# espnative-deadrail-2-1.net
KiCad netlist of a schematic drawn in EAGLE
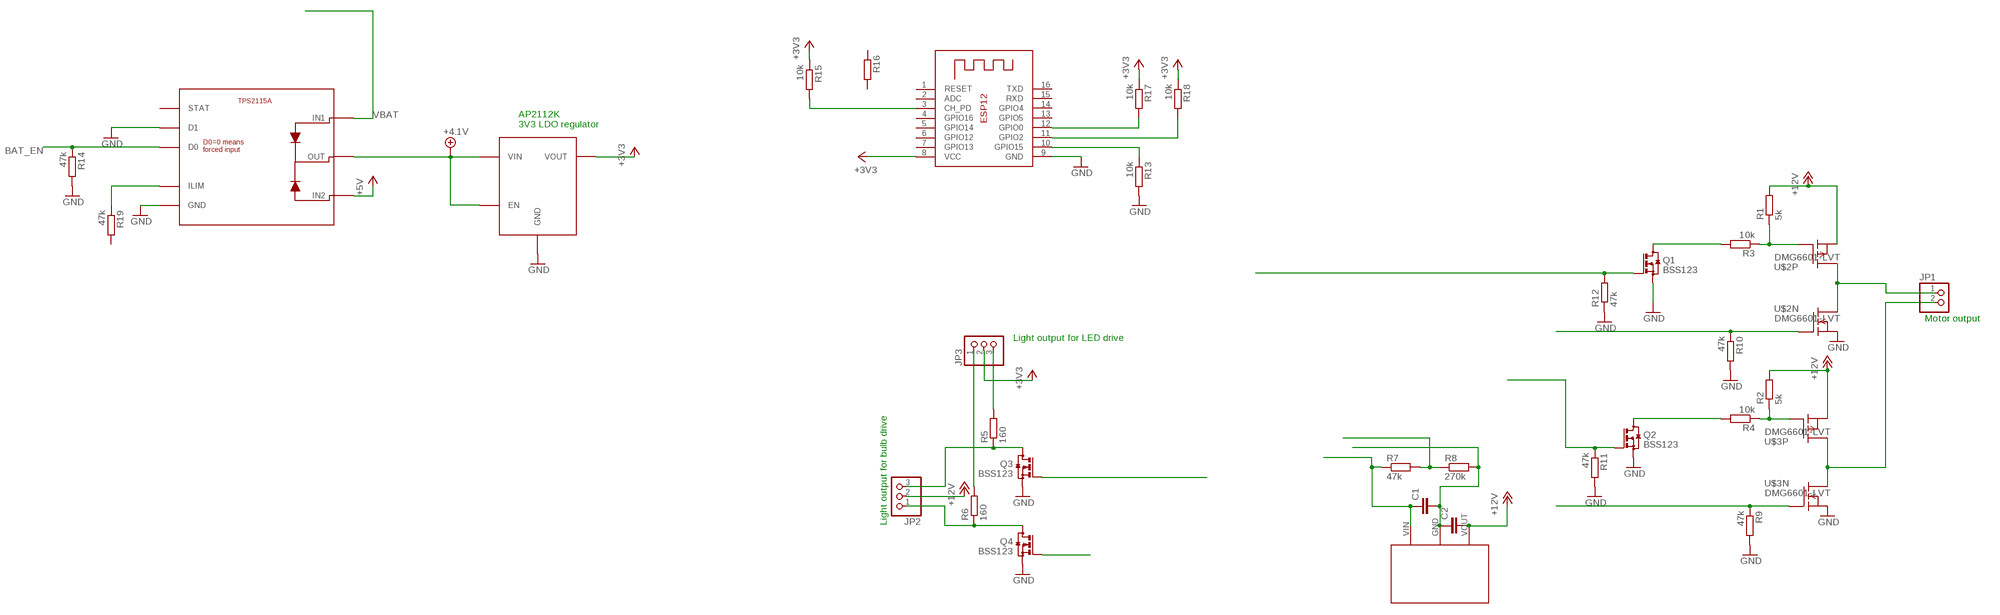
[diagram p0: schematic, sheet 1]

(export (version "E")
  (design (tool "Eeschema 10.0.6"))
  (components
    (comp (ref "C1")
      (value "C-EUC1210")
      (footprint "eagle-import:C1210")
      (libsource (lib "eagle-import") (part "C-EUC1210"))
    )
    (comp (ref "C2")
      (value "C-EUC1210")
      (footprint "eagle-import:C1210")
      (libsource (lib "eagle-import") (part "C-EUC1210"))
    )
    (comp (ref "JP1")
      (value "PINHD-1X2")
      (footprint "eagle-import:1X02")
      (libsource (lib "eagle-import") (part "PINHD-1X2"))
    )
    (comp (ref "JP2")
      (value "PINHD-1X3")
      (footprint "eagle-import:1X03")
      (libsource (lib "eagle-import") (part "PINHD-1X3"))
    )
    (comp (ref "JP3")
      (value "PINHD-1X3")
      (footprint "eagle-import:1X03")
      (libsource (lib "eagle-import") (part "PINHD-1X3"))
    )
    (comp (ref "Q1")
      (value "BSS123")
      (footprint "eagle-import:SOT23")
      (libsource (lib "eagle-import") (part "BSS123"))
    )
    (comp (ref "Q2")
      (value "BSS123")
      (footprint "eagle-import:SOT23")
      (libsource (lib "eagle-import") (part "BSS123"))
    )
    (comp (ref "Q3")
      (value "BSS123")
      (footprint "eagle-import:SOT23")
      (libsource (lib "eagle-import") (part "BSS123"))
    )
    (comp (ref "Q4")
      (value "BSS123")
      (footprint "eagle-import:SOT23")
      (libsource (lib "eagle-import") (part "BSS123"))
    )
    (comp (ref "R1")
      (value "5k")
      (footprint "eagle-import:R0805")
      (libsource (lib "eagle-import") (part "R-EU_R0805"))
    )
    (comp (ref "R2")
      (value "5k")
      (footprint "eagle-import:R0805")
      (libsource (lib "eagle-import") (part "R-EU_R0805"))
    )
    (comp (ref "R3")
      (value "10k")
      (footprint "eagle-import:R0805")
      (libsource (lib "eagle-import") (part "R-EU_R0805"))
    )
    (comp (ref "R4")
      (value "10k")
      (footprint "eagle-import:R0805")
      (libsource (lib "eagle-import") (part "R-EU_R0805"))
    )
    (comp (ref "R5")
      (value "160")
      (footprint "eagle-import:R0805")
      (libsource (lib "eagle-import") (part "R-EU_R0805"))
    )
    (comp (ref "R6")
      (value "160")
      (footprint "eagle-import:R0805")
      (libsource (lib "eagle-import") (part "R-EU_R0805"))
    )
    (comp (ref "R7")
      (value "47k")
      (footprint "eagle-import:R0805")
      (libsource (lib "eagle-import") (part "R-EU_R0805"))
    )
    (comp (ref "R8")
      (value "270k")
      (footprint "eagle-import:R0805")
      (libsource (lib "eagle-import") (part "R-EU_R0805"))
    )
    (comp (ref "R9")
      (value "47k")
      (footprint "eagle-import:R0805")
      (libsource (lib "eagle-import") (part "R-EU_R0805"))
    )
    (comp (ref "R10")
      (value "47k")
      (footprint "eagle-import:R0805")
      (libsource (lib "eagle-import") (part "R-EU_R0805"))
    )
    (comp (ref "R11")
      (value "47k")
      (footprint "eagle-import:R0805")
      (libsource (lib "eagle-import") (part "R-EU_R0805"))
    )
    (comp (ref "R12")
      (value "47k")
      (footprint "eagle-import:R0805")
      (libsource (lib "eagle-import") (part "R-EU_R0805"))
    )
    (comp (ref "R13")
      (value "10k")
      (footprint "eagle-import:R0603")
      (libsource (lib "eagle-import") (part "R-EU_R0603"))
    )
    (comp (ref "R14")
      (value "47k")
      (footprint "eagle-import:R0603")
      (libsource (lib "eagle-import") (part "R-EU_R0603"))
    )
    (comp (ref "R15")
      (value "10k")
      (footprint "eagle-import:R0603")
      (libsource (lib "eagle-import") (part "R-EU_R0603"))
    )
    (comp (ref "R16")
      (value "R-EU_R0603")
      (footprint "eagle-import:R0603")
      (libsource (lib "eagle-import") (part "R-EU_R0603"))
    )
    (comp (ref "R17")
      (value "10k")
      (footprint "eagle-import:R0603")
      (libsource (lib "eagle-import") (part "R-EU_R0603"))
    )
    (comp (ref "R18")
      (value "10k")
      (footprint "eagle-import:R0603")
      (libsource (lib "eagle-import") (part "R-EU_R0603"))
    )
    (comp (ref "R19")
      (value "47k")
      (footprint "eagle-import:R0603")
      (libsource (lib "eagle-import") (part "R-EU_R0603"))
    )
    (comp (ref "U$1")
      (value "AP2112K-3V3")
      (footprint "eagle-import:SOT23-5L")
      (libsource (lib "eagle-import") (part "AP2112K"))
    )
    (comp (ref "U$2")
      (value "DMG6601-LVT")
      (footprint "eagle-import:TSOT-26")
      (libsource (lib "eagle-import") (part "DMG6601-LVT"))
    )
    (comp (ref "U$3")
      (value "DMG6601-LVT")
      (footprint "eagle-import:TSOT-26")
      (libsource (lib "eagle-import") (part "DMG6601-LVT"))
    )
    (comp (ref "U$4")
      (value "TPS2115A")
      (footprint "eagle-import:TSSOP-8")
      (libsource (lib "eagle-import") (part "TPS2115A"))
    )
    (comp (ref "U$5")
      (value "POLOLU-VREG12")
      (footprint "eagle-import:POLOLU-REGULATOR")
      (libsource (lib "eagle-import") (part "POLOLU-VREG12"))
    )
    (comp (ref "X1")
      (value "ESP-12")
      (footprint "eagle-import:ESP-12")
      (libsource (lib "eagle-import") (part "ESP-12"))
    )
  )
  (nets
    (net (code "1") (name "+3V3") (class "Default")
      (node (ref "JP3") (pin "2") (pinfunction "2_2") (pintype "passive"))
      (node (ref "R15") (pin "1") (pinfunction "1_1") (pintype "passive"))
      (node (ref "R17") (pin "1") (pinfunction "1_1") (pintype "passive"))
      (node (ref "R18") (pin "1") (pinfunction "1_1") (pintype "passive"))
      (node (ref "U$1") (pin "5") (pinfunction "VOUT_5") (pintype "bidirectional"))
      (node (ref "X1") (pin "8") (pinfunction "VCC_8") (pintype "power_in"))
    )
    (net (code "2") (name "+4.1V") (class "Default")
      (node (ref "U$1") (pin "1") (pinfunction "VIN_1") (pintype "bidirectional"))
      (node (ref "U$1") (pin "3") (pinfunction "EN_3") (pintype "bidirectional"))
      (node (ref "U$4") (pin "7") (pinfunction "OUT_7") (pintype "bidirectional"))
    )
    (net (code "3") (name "+5V") (class "Default")
      (node (ref "U$4") (pin "6") (pinfunction "IN2_6") (pintype "bidirectional"))
    )
    (net (code "4") (name "+12V") (class "Default")
      (node (ref "C2") (pin "2") (pinfunction "2_2") (pintype "passive"))
      (node (ref "JP2") (pin "2") (pinfunction "2_2") (pintype "passive"))
      (node (ref "R1") (pin "2") (pinfunction "2_2") (pintype "passive"))
      (node (ref "R2") (pin "2") (pinfunction "2_2") (pintype "passive"))
      (node (ref "U$2") (pin "2") (pinfunction "S_2") (pintype "passive"))
      (node (ref "U$3") (pin "2") (pinfunction "S_2") (pintype "passive"))
      (node (ref "U$5") (pin "VOUT") (pinfunction "VOUT_VOUT") (pintype "bidirectional"))
    )
    (net (code "5") (name "/BAT_EN") (class "Default")
      (node (ref "R14") (pin "1") (pinfunction "1_1") (pintype "passive"))
      (node (ref "U$4") (pin "2") (pinfunction "D0_2") (pintype "bidirectional"))
    )
    (net (code "6") (name "/VBAT") (class "Default")
      (node (ref "C1") (pin "1") (pinfunction "1_1") (pintype "passive"))
      (node (ref "R7") (pin "1") (pinfunction "1_1") (pintype "passive"))
      (node (ref "U$4") (pin "8") (pinfunction "IN1_8") (pintype "bidirectional"))
      (node (ref "U$5") (pin "VIN") (pinfunction "VIN_VIN") (pintype "bidirectional"))
    )
    (net (code "7") (name "GND") (class "Default")
      (node (ref "C1") (pin "2") (pinfunction "2_2") (pintype "passive"))
      (node (ref "C2") (pin "1") (pinfunction "1_1") (pintype "passive"))
      (node (ref "Q1") (pin "2") (pinfunction "S_2") (pintype "passive"))
      (node (ref "Q2") (pin "2") (pinfunction "S_2") (pintype "passive"))
      (node (ref "Q3") (pin "2") (pinfunction "S_2") (pintype "passive"))
      (node (ref "Q4") (pin "2") (pinfunction "S_2") (pintype "passive"))
      (node (ref "R10") (pin "2") (pinfunction "2_2") (pintype "passive"))
      (node (ref "R11") (pin "2") (pinfunction "2_2") (pintype "passive"))
      (node (ref "R12") (pin "1") (pinfunction "1_1") (pintype "passive"))
      (node (ref "R13") (pin "2") (pinfunction "2_2") (pintype "passive"))
      (node (ref "R14") (pin "2") (pinfunction "2_2") (pintype "passive"))
      (node (ref "R8") (pin "2") (pinfunction "2_2") (pintype "passive"))
      (node (ref "R9") (pin "2") (pinfunction "2_2") (pintype "passive"))
      (node (ref "U$1") (pin "2") (pinfunction "GND_2") (pintype "bidirectional"))
      (node (ref "U$2") (pin "5") (pinfunction "S_5") (pintype "passive"))
      (node (ref "U$3") (pin "5") (pinfunction "S_5") (pintype "passive"))
      (node (ref "U$4") (pin "3") (pinfunction "D1_3") (pintype "bidirectional"))
      (node (ref "U$4") (pin "5") (pinfunction "GND_5") (pintype "bidirectional"))
      (node (ref "U$5") (pin "GND") (pinfunction "GND_GND") (pintype "bidirectional"))
      (node (ref "X1") (pin "9") (pinfunction "GND_9") (pintype "power_in"))
    )
    (net (code "8") (name "Net-(JP3-Pad1)") (class "Default")
      (node (ref "JP3") (pin "1") (pinfunction "1_1") (pintype "passive"))
      (node (ref "R6") (pin "2") (pinfunction "2_2") (pintype "passive"))
    )
    (net (code "9") (name "Net-(JP3-Pad3)") (class "Default")
      (node (ref "JP3") (pin "3") (pinfunction "3_3") (pintype "passive"))
      (node (ref "R5") (pin "2") (pinfunction "2_2") (pintype "passive"))
    )
    (net (code "10") (name "Net-(Q1-D)") (class "Default")
      (node (ref "Q1") (pin "3") (pinfunction "D_3") (pintype "passive"))
      (node (ref "R3") (pin "2") (pinfunction "2_2") (pintype "passive"))
    )
    (net (code "11") (name "Net-(Q1-G)") (class "Default")
      (node (ref "Q1") (pin "1") (pinfunction "G_1") (pintype "passive"))
      (node (ref "R12") (pin "2") (pinfunction "2_2") (pintype "passive"))
    )
    (net (code "12") (name "Net-(Q2-D)") (class "Default")
      (node (ref "Q2") (pin "3") (pinfunction "D_3") (pintype "passive"))
      (node (ref "R4") (pin "2") (pinfunction "2_2") (pintype "passive"))
    )
    (net (code "13") (name "Net-(Q2-G)") (class "Default")
      (node (ref "Q2") (pin "1") (pinfunction "G_1") (pintype "passive"))
      (node (ref "R11") (pin "1") (pinfunction "1_1") (pintype "passive"))
    )
    (net (code "14") (name "Net-(Q3-D)") (class "Default")
      (node (ref "JP2") (pin "3") (pinfunction "3_3") (pintype "passive"))
      (node (ref "Q3") (pin "3") (pinfunction "D_3") (pintype "passive"))
      (node (ref "R5") (pin "1") (pinfunction "1_1") (pintype "passive"))
    )
    (net (code "15") (name "Net-(Q4-D)") (class "Default")
      (node (ref "JP2") (pin "1") (pinfunction "1_1") (pintype "passive"))
      (node (ref "Q4") (pin "3") (pinfunction "D_3") (pintype "passive"))
      (node (ref "R6") (pin "1") (pinfunction "1_1") (pintype "passive"))
    )
    (net (code "16") (name "Net-(R7-Pad2)") (class "Default")
      (node (ref "R7") (pin "2") (pinfunction "2_2") (pintype "passive"))
      (node (ref "R8") (pin "1") (pinfunction "1_1") (pintype "passive"))
    )
    (net (code "17") (name "Net-(U$2A-D)") (class "Default")
      (node (ref "JP1") (pin "1") (pinfunction "1_1") (pintype "passive"))
      (node (ref "U$2") (pin "4") (pinfunction "D_4") (pintype "passive"))
      (node (ref "U$2") (pin "6") (pinfunction "D_6") (pintype "passive"))
    )
    (net (code "18") (name "Net-(U$2A-G)") (class "Default")
      (node (ref "R10") (pin "1") (pinfunction "1_1") (pintype "passive"))
      (node (ref "U$2") (pin "1") (pinfunction "G_1") (pintype "passive"))
    )
    (net (code "19") (name "Net-(U$2B-G)") (class "Default")
      (node (ref "R1") (pin "1") (pinfunction "1_1") (pintype "passive"))
      (node (ref "R3") (pin "1") (pinfunction "1_1") (pintype "passive"))
      (node (ref "U$2") (pin "3") (pinfunction "G_3") (pintype "passive"))
    )
    (net (code "20") (name "Net-(U$3A-D)") (class "Default")
      (node (ref "JP1") (pin "2") (pinfunction "2_2") (pintype "passive"))
      (node (ref "U$3") (pin "4") (pinfunction "D_4") (pintype "passive"))
      (node (ref "U$3") (pin "6") (pinfunction "D_6") (pintype "passive"))
    )
    (net (code "21") (name "Net-(U$3A-G)") (class "Default")
      (node (ref "R9") (pin "1") (pinfunction "1_1") (pintype "passive"))
      (node (ref "U$3") (pin "1") (pinfunction "G_1") (pintype "passive"))
    )
    (net (code "22") (name "Net-(U$3B-G)") (class "Default")
      (node (ref "R2") (pin "1") (pinfunction "1_1") (pintype "passive"))
      (node (ref "R4") (pin "1") (pinfunction "1_1") (pintype "passive"))
      (node (ref "U$3") (pin "3") (pinfunction "G_3") (pintype "passive"))
    )
    (net (code "23") (name "Net-(U$4-ILIM)") (class "Default")
      (node (ref "R19") (pin "1") (pinfunction "1_1") (pintype "passive"))
      (node (ref "U$4") (pin "4") (pinfunction "ILIM_4") (pintype "bidirectional"))
    )
    (net (code "24") (name "Net-(X1-CH_PD)") (class "Default")
      (node (ref "R15") (pin "2") (pinfunction "2_2") (pintype "passive"))
      (node (ref "X1") (pin "3") (pinfunction "CH_PD_3") (pintype "input"))
    )
    (net (code "25") (name "Net-(X1-GPIO0)") (class "Default")
      (node (ref "R17") (pin "2") (pinfunction "2_2") (pintype "passive"))
      (node (ref "X1") (pin "12") (pinfunction "GPIO0_12") (pintype "bidirectional"))
    )
    (net (code "26") (name "Net-(X1-GPIO2)") (class "Default")
      (node (ref "R18") (pin "2") (pinfunction "2_2") (pintype "passive"))
      (node (ref "X1") (pin "11") (pinfunction "GPIO2_11") (pintype "bidirectional"))
    )
    (net (code "27") (name "Net-(X1-GPIO15)") (class "Default")
      (node (ref "R13") (pin "1") (pinfunction "1_1") (pintype "passive"))
      (node (ref "X1") (pin "10") (pinfunction "GPIO15_10") (pintype "bidirectional"))
    )
    (net (code "28") (name "unconnected-(Q3-G-Pad1)") (class "Default")
      (node (ref "Q3") (pin "1") (pinfunction "G_1") (pintype "passive"))
    )
    (net (code "29") (name "unconnected-(Q4-G-Pad1)") (class "Default")
      (node (ref "Q4") (pin "1") (pinfunction "G_1") (pintype "passive"))
    )
    (net (code "30") (name "unconnected-(R16-Pad1)") (class "Default")
      (node (ref "R16") (pin "1") (pinfunction "1_1") (pintype "passive"))
    )
    (net (code "31") (name "unconnected-(R16-Pad2)") (class "Default")
      (node (ref "R16") (pin "2") (pinfunction "2_2") (pintype "passive"))
    )
    (net (code "32") (name "unconnected-(R19-Pad2)") (class "Default")
      (node (ref "R19") (pin "2") (pinfunction "2_2") (pintype "passive"))
    )
    (net (code "33") (name "unconnected-(U$4-STAT-Pad1)") (class "Default")
      (node (ref "U$4") (pin "1") (pinfunction "STAT_1") (pintype "bidirectional"))
    )
    (net (code "34") (name "unconnected-(X1-ADC-Pad2)") (class "Default")
      (node (ref "X1") (pin "2") (pinfunction "ADC_2") (pintype "passive"))
    )
    (net (code "35") (name "unconnected-(X1-GPIO4-Pad14)") (class "Default")
      (node (ref "X1") (pin "14") (pinfunction "GPIO4_14") (pintype "bidirectional"))
    )
    (net (code "36") (name "unconnected-(X1-GPIO5-Pad13)") (class "Default")
      (node (ref "X1") (pin "13") (pinfunction "GPIO5_13") (pintype "bidirectional"))
    )
    (net (code "37") (name "unconnected-(X1-GPIO12-Pad6)") (class "Default")
      (node (ref "X1") (pin "6") (pinfunction "GPIO12_6") (pintype "bidirectional"))
    )
    (net (code "38") (name "unconnected-(X1-GPIO13-Pad7)") (class "Default")
      (node (ref "X1") (pin "7") (pinfunction "GPIO13_7") (pintype "bidirectional"))
    )
    (net (code "39") (name "unconnected-(X1-GPIO14-Pad5)") (class "Default")
      (node (ref "X1") (pin "5") (pinfunction "GPIO14_5") (pintype "bidirectional"))
    )
    (net (code "40") (name "unconnected-(X1-GPIO16-Pad4)") (class "Default")
      (node (ref "X1") (pin "4") (pinfunction "GPIO16_4") (pintype "bidirectional"))
    )
    (net (code "41") (name "unconnected-(X1-RESET-Pad1)") (class "Default")
      (node (ref "X1") (pin "1") (pinfunction "RESET_1") (pintype "input"))
    )
    (net (code "42") (name "unconnected-(X1-RXD-Pad15)") (class "Default")
      (node (ref "X1") (pin "15") (pinfunction "RXD_15") (pintype "input"))
    )
    (net (code "43") (name "unconnected-(X1-TXD-Pad16)") (class "Default")
      (node (ref "X1") (pin "16") (pinfunction "TXD_16") (pintype "output"))
    )
  )
)
